# mcu.net
KiCad netlist of a schematic drawn in Altium Designer
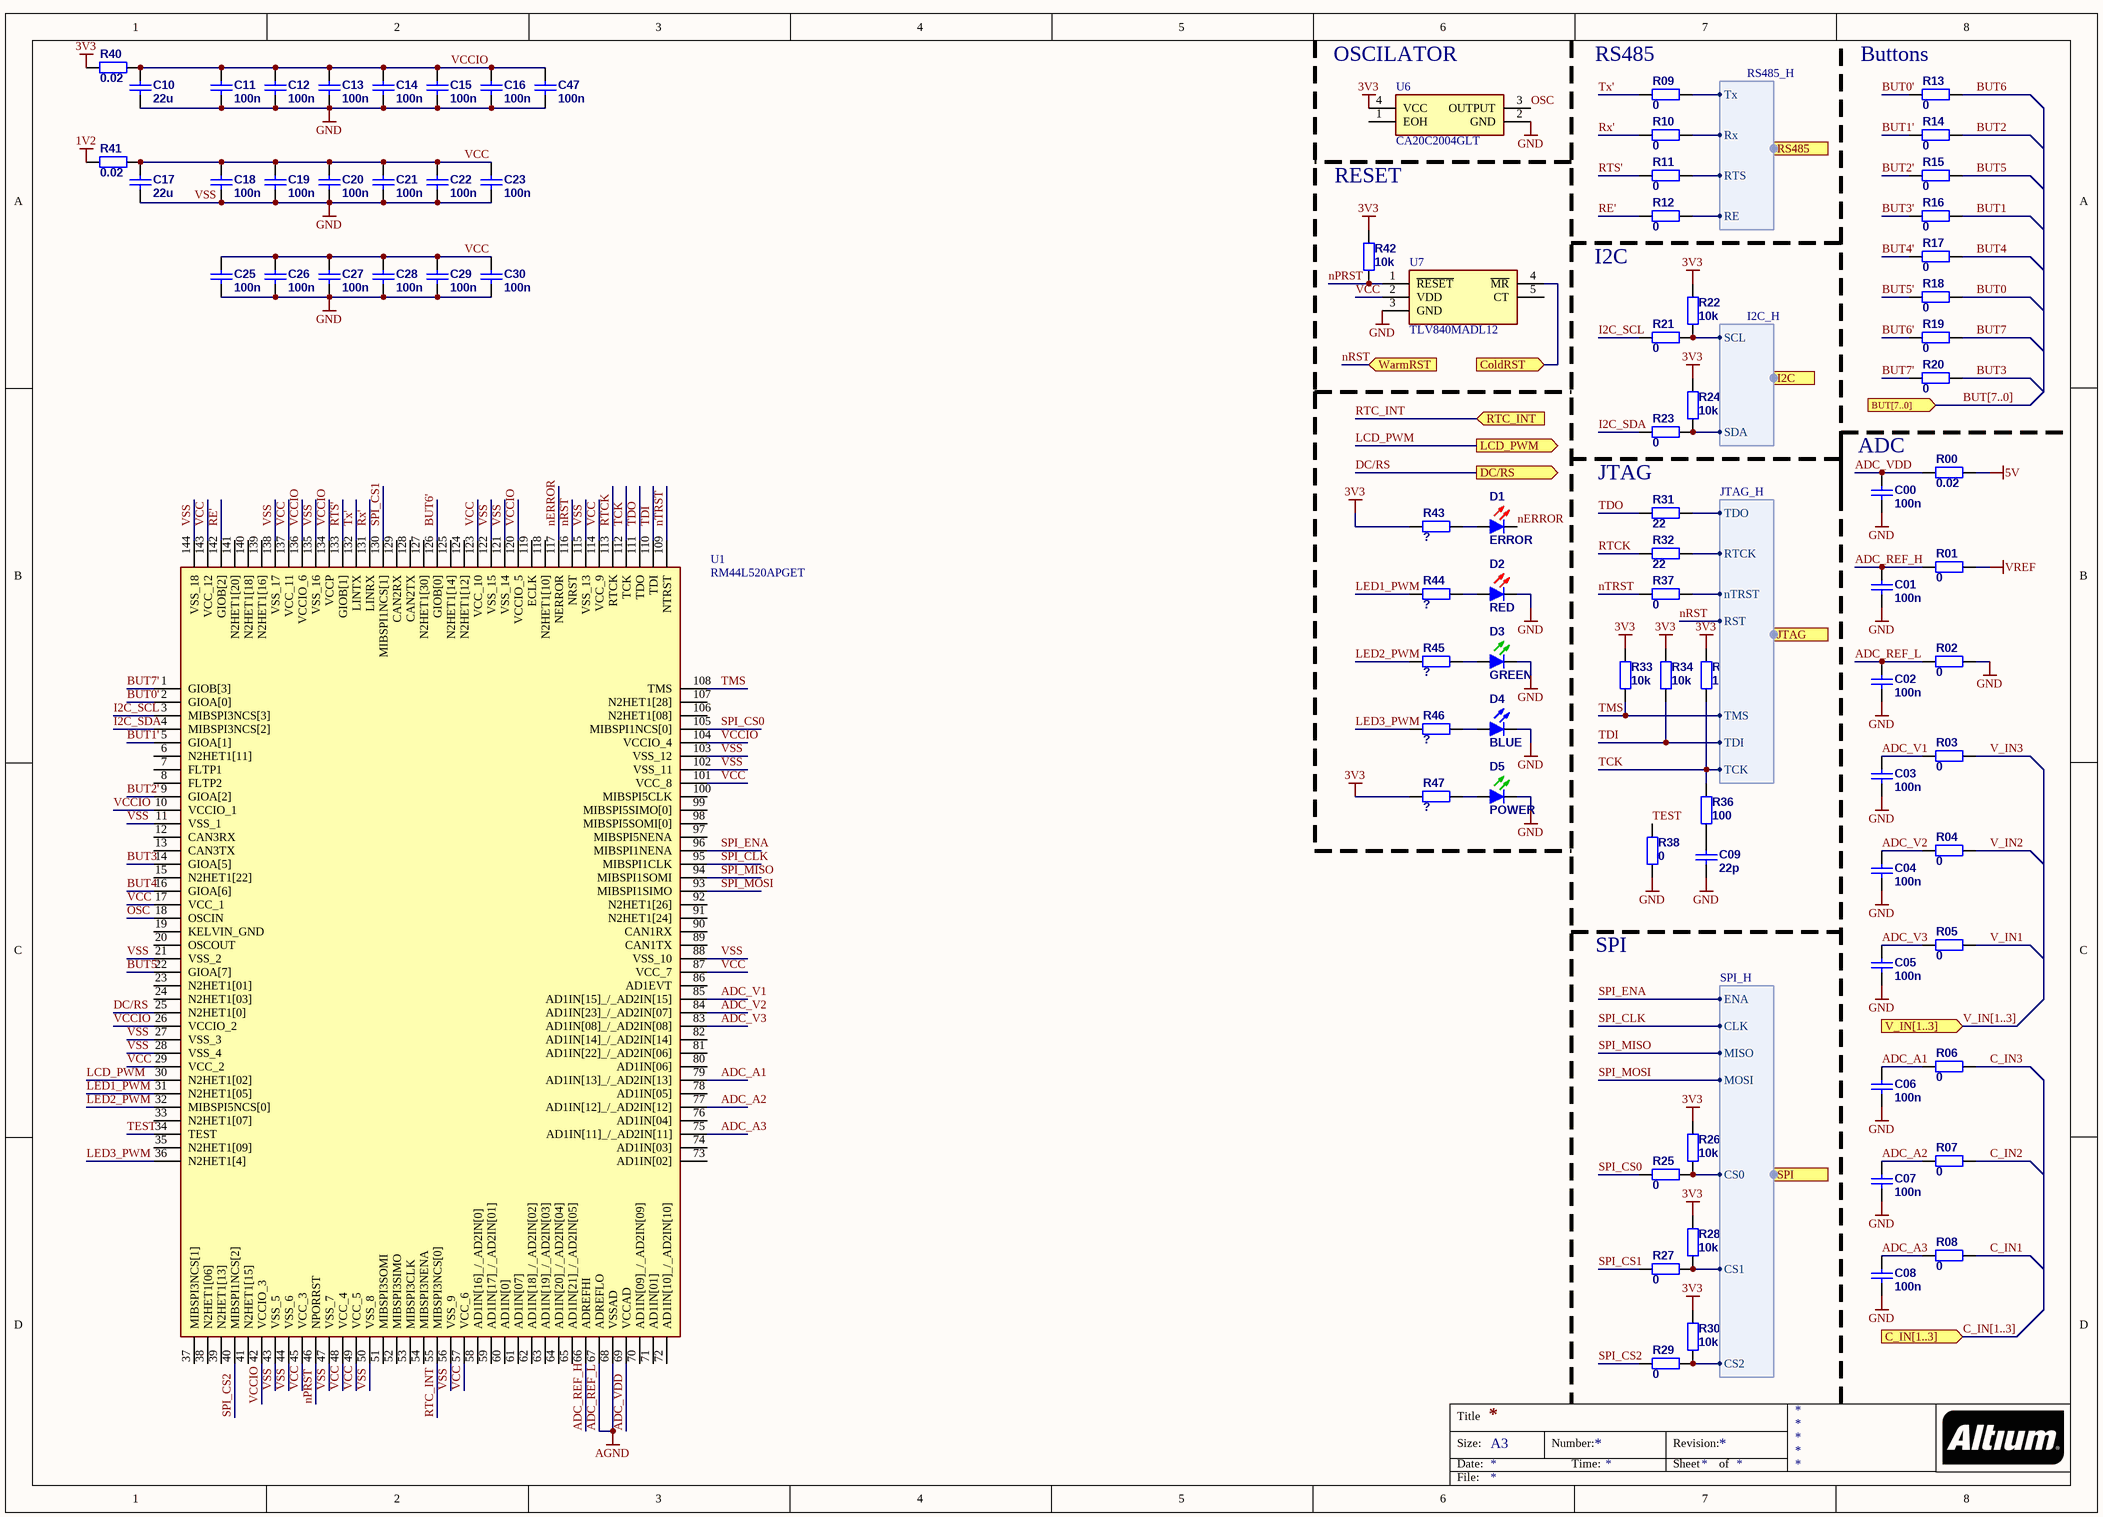
[diagram p0: mcu.SchDoc]

(export (version "E")
  (design (tool "Eeschema 10.0.6"))
  (components
    (comp (ref "C00")
      (value "100n")
      (footprint "C0402")
      (description "Capacitor")
      (libsource (lib "capacitors") (part "Cap"))
    )
    (comp (ref "C01")
      (value "100n")
      (footprint "C0402")
      (description "Capacitor")
      (libsource (lib "capacitors") (part "Cap"))
    )
    (comp (ref "C02")
      (value "100n")
      (footprint "C0402")
      (description "Capacitor")
      (libsource (lib "capacitors") (part "Cap"))
    )
    (comp (ref "C03")
      (value "100n")
      (footprint "C0402")
      (description "Capacitor")
      (libsource (lib "capacitors") (part "Cap"))
    )
    (comp (ref "C04")
      (value "100n")
      (footprint "C0402")
      (description "Capacitor")
      (libsource (lib "capacitors") (part "Cap"))
    )
    (comp (ref "C05")
      (value "100n")
      (footprint "C0402")
      (description "Capacitor")
      (libsource (lib "capacitors") (part "Cap"))
    )
    (comp (ref "C06")
      (value "100n")
      (footprint "C0402")
      (description "Capacitor")
      (libsource (lib "capacitors") (part "Cap"))
    )
    (comp (ref "C07")
      (value "100n")
      (footprint "C0402")
      (description "Capacitor")
      (libsource (lib "capacitors") (part "Cap"))
    )
    (comp (ref "C08")
      (value "100n")
      (footprint "C0402")
      (description "Capacitor")
      (libsource (lib "capacitors") (part "Cap"))
    )
    (comp (ref "C09")
      (value "22p")
      (footprint "C0402")
      (description "Capacitor")
      (libsource (lib "capacitors") (part "Cap"))
    )
    (comp (ref "C10")
      (value "22u")
      (footprint "C0603")
      (description "Capacitor")
      (libsource (lib "capacitors") (part "Cap"))
    )
    (comp (ref "C11")
      (value "100n")
      (footprint "C0402")
      (description "Capacitor")
      (libsource (lib "capacitors") (part "Cap"))
    )
    (comp (ref "C12")
      (value "100n")
      (footprint "C0402")
      (description "Capacitor")
      (libsource (lib "capacitors") (part "Cap"))
    )
    (comp (ref "C13")
      (value "100n")
      (footprint "C0402")
      (description "Capacitor")
      (libsource (lib "capacitors") (part "Cap"))
    )
    (comp (ref "C14")
      (value "100n")
      (footprint "C0402")
      (description "Capacitor")
      (libsource (lib "capacitors") (part "Cap"))
    )
    (comp (ref "C15")
      (value "100n")
      (footprint "C0402")
      (description "Capacitor")
      (libsource (lib "capacitors") (part "Cap"))
    )
    (comp (ref "C16")
      (value "100n")
      (footprint "C0402")
      (description "Capacitor")
      (libsource (lib "capacitors") (part "Cap"))
    )
    (comp (ref "C17")
      (value "22u")
      (footprint "C0603")
      (description "Capacitor")
      (libsource (lib "capacitors") (part "Cap"))
    )
    (comp (ref "C18")
      (value "100n")
      (footprint "C0402")
      (description "Capacitor")
      (libsource (lib "capacitors") (part "Cap"))
    )
    (comp (ref "C19")
      (value "100n")
      (footprint "C0402")
      (description "Capacitor")
      (libsource (lib "capacitors") (part "Cap"))
    )
    (comp (ref "C20")
      (value "100n")
      (footprint "C0402")
      (description "Capacitor")
      (libsource (lib "capacitors") (part "Cap"))
    )
    (comp (ref "C21")
      (value "100n")
      (footprint "C0402")
      (description "Capacitor")
      (libsource (lib "capacitors") (part "Cap"))
    )
    (comp (ref "C22")
      (value "100n")
      (footprint "C0402")
      (description "Capacitor")
      (libsource (lib "capacitors") (part "Cap"))
    )
    (comp (ref "C23")
      (value "100n")
      (footprint "C0402")
      (description "Capacitor")
      (libsource (lib "capacitors") (part "Cap"))
    )
    (comp (ref "C25")
      (value "100n")
      (footprint "C0402")
      (description "Capacitor")
      (libsource (lib "capacitors") (part "Cap"))
    )
    (comp (ref "C26")
      (value "100n")
      (footprint "C0402")
      (description "Capacitor")
      (libsource (lib "capacitors") (part "Cap"))
    )
    (comp (ref "C27")
      (value "100n")
      (footprint "C0402")
      (description "Capacitor")
      (libsource (lib "capacitors") (part "Cap"))
    )
    (comp (ref "C28")
      (value "100n")
      (footprint "C0402")
      (description "Capacitor")
      (libsource (lib "capacitors") (part "Cap"))
    )
    (comp (ref "C29")
      (value "100n")
      (footprint "C0402")
      (description "Capacitor")
      (libsource (lib "capacitors") (part "Cap"))
    )
    (comp (ref "C30")
      (value "100n")
      (footprint "C0402")
      (description "Capacitor")
      (libsource (lib "capacitors") (part "Cap"))
    )
    (comp (ref "C47")
      (value "100n")
      (footprint "C0402")
      (description "Capacitor")
      (libsource (lib "capacitors") (part "Cap"))
    )
    (comp (ref "D1")
      (value "ERROR")
      (footprint "LED1206R")
      (description "RED LED")
      (libsource (lib "leds") (part "LED_RED"))
    )
    (comp (ref "D2")
      (value "RED")
      (footprint "LED1206R")
      (description "RED LED")
      (libsource (lib "leds") (part "LED_RED"))
    )
    (comp (ref "D3")
      (value "GREEN")
      (footprint "LED1206G")
      (description "GREEN LED")
      (libsource (lib "leds") (part "LED_GREEN"))
    )
    (comp (ref "D4")
      (value "BLUE")
      (footprint "LED1206B")
      (description "BLUE LED")
      (libsource (lib "leds") (part "LED_BLUE"))
    )
    (comp (ref "D5")
      (value "POWER")
      (footprint "LED1206G")
      (description "GREEN LED")
      (libsource (lib "leds") (part "LED_GREEN"))
    )
    (comp (ref "R00")
      (value "0.02")
      (footprint "R0402")
      (description "Resistor")
      (libsource (lib "resistors") (part "Res"))
    )
    (comp (ref "R01")
      (value "0")
      (footprint "R0402")
      (description "Resistor")
      (libsource (lib "resistors") (part "Res"))
    )
    (comp (ref "R02")
      (value "0")
      (footprint "R0402")
      (description "Resistor")
      (libsource (lib "resistors") (part "Res"))
    )
    (comp (ref "R03")
      (value "0")
      (footprint "R0402")
      (description "Resistor")
      (libsource (lib "resistors") (part "Res"))
    )
    (comp (ref "R04")
      (value "0")
      (footprint "R0402")
      (description "Resistor")
      (libsource (lib "resistors") (part "Res"))
    )
    (comp (ref "R05")
      (value "0")
      (footprint "R0402")
      (description "Resistor")
      (libsource (lib "resistors") (part "Res"))
    )
    (comp (ref "R06")
      (value "0")
      (footprint "R0402")
      (description "Resistor")
      (libsource (lib "resistors") (part "Res"))
    )
    (comp (ref "R07")
      (value "0")
      (footprint "R0402")
      (description "Resistor")
      (libsource (lib "resistors") (part "Res"))
    )
    (comp (ref "R08")
      (value "0")
      (footprint "R0402")
      (description "Resistor")
      (libsource (lib "resistors") (part "Res"))
    )
    (comp (ref "R09")
      (value "0")
      (footprint "R0402")
      (description "Resistor")
      (libsource (lib "resistors") (part "Res"))
    )
    (comp (ref "R10")
      (value "0")
      (footprint "R0402")
      (description "Resistor")
      (libsource (lib "resistors") (part "Res"))
    )
    (comp (ref "R11")
      (value "0")
      (footprint "R0402")
      (description "Resistor")
      (libsource (lib "resistors") (part "Res"))
    )
    (comp (ref "R12")
      (value "0")
      (footprint "R0402")
      (description "Resistor")
      (libsource (lib "resistors") (part "Res"))
    )
    (comp (ref "R13")
      (value "0")
      (footprint "R0402")
      (description "Resistor")
      (libsource (lib "resistors") (part "Res"))
    )
    (comp (ref "R14")
      (value "0")
      (footprint "R0402")
      (description "Resistor")
      (libsource (lib "resistors") (part "Res"))
    )
    (comp (ref "R15")
      (value "0")
      (footprint "R0402")
      (description "Resistor")
      (libsource (lib "resistors") (part "Res"))
    )
    (comp (ref "R16")
      (value "0")
      (footprint "R0402")
      (description "Resistor")
      (libsource (lib "resistors") (part "Res"))
    )
    (comp (ref "R17")
      (value "0")
      (footprint "R0402")
      (description "Resistor")
      (libsource (lib "resistors") (part "Res"))
    )
    (comp (ref "R18")
      (value "0")
      (footprint "R0402")
      (description "Resistor")
      (libsource (lib "resistors") (part "Res"))
    )
    (comp (ref "R19")
      (value "0")
      (footprint "R0402")
      (description "Resistor")
      (libsource (lib "resistors") (part "Res"))
    )
    (comp (ref "R20")
      (value "0")
      (footprint "R0402")
      (description "Resistor")
      (libsource (lib "resistors") (part "Res"))
    )
    (comp (ref "R21")
      (value "0")
      (footprint "R0402")
      (description "Resistor")
      (libsource (lib "resistors") (part "Res"))
    )
    (comp (ref "R22")
      (value "10k")
      (footprint "R0402")
      (description "Resistor")
      (libsource (lib "") (part "Res_1"))
    )
    (comp (ref "R23")
      (value "0")
      (footprint "R0402")
      (description "Resistor")
      (libsource (lib "") (part "Res_2"))
    )
    (comp (ref "R24")
      (value "10k")
      (footprint "R0402")
      (description "Resistor")
      (libsource (lib "") (part "Res_3"))
    )
    (comp (ref "R25")
      (value "0")
      (footprint "R0402")
      (description "Resistor")
      (libsource (lib "resistors") (part "Res"))
    )
    (comp (ref "R26")
      (value "10k")
      (footprint "R0402")
      (description "Resistor")
      (libsource (lib "") (part "Res_1"))
    )
    (comp (ref "R27")
      (value "0")
      (footprint "R0402")
      (description "Resistor")
      (libsource (lib "") (part "Res_2"))
    )
    (comp (ref "R28")
      (value "10k")
      (footprint "R0402")
      (description "Resistor")
      (libsource (lib "") (part "Res_1"))
    )
    (comp (ref "R29")
      (value "0")
      (footprint "R0402")
      (description "Resistor")
      (libsource (lib "") (part "Res_2"))
    )
    (comp (ref "R30")
      (value "10k")
      (footprint "R0402")
      (description "Resistor")
      (libsource (lib "") (part "Res_3"))
    )
    (comp (ref "R31")
      (value "22")
      (footprint "R0402")
      (description "Resistor")
      (libsource (lib "resistors") (part "Res"))
    )
    (comp (ref "R32")
      (value "22")
      (footprint "R0402")
      (description "Resistor")
      (libsource (lib "resistors") (part "Res"))
    )
    (comp (ref "R33")
      (value "10k")
      (footprint "R0402")
      (description "Resistor")
      (libsource (lib "") (part "Res_1"))
    )
    (comp (ref "R34")
      (value "10k")
      (footprint "R0402")
      (description "Resistor")
      (libsource (lib "") (part "Res_1"))
    )
    (comp (ref "R35")
      (value "10k")
      (footprint "R0402")
      (description "Resistor")
      (libsource (lib "") (part "Res_1"))
    )
    (comp (ref "R36")
      (value "100")
      (footprint "R0402")
      (description "Resistor")
      (libsource (lib "") (part "Res_1"))
    )
    (comp (ref "R37")
      (value "0")
      (footprint "R0402")
      (description "Resistor")
      (libsource (lib "resistors") (part "Res"))
    )
    (comp (ref "R38")
      (value "0")
      (footprint "R0402")
      (description "Resistor")
      (libsource (lib "") (part "Res_1"))
    )
    (comp (ref "R40")
      (value "0.02")
      (footprint "R0603")
      (description "Resistor")
      (libsource (lib "resistors") (part "Res"))
    )
    (comp (ref "R41")
      (value "0.02")
      (footprint "R0603")
      (description "Resistor")
      (libsource (lib "resistors") (part "Res"))
    )
    (comp (ref "R42")
      (value "10k")
      (footprint "R0402")
      (description "Resistor")
      (libsource (lib "") (part "Res_1"))
    )
    (comp (ref "R43")
      (value "?")
      (footprint "R0603")
      (description "Resistor")
      (libsource (lib "") (part "Res_2"))
    )
    (comp (ref "R44")
      (value "?")
      (footprint "R0402")
      (description "Resistor")
      (libsource (lib "") (part "Res_2"))
    )
    (comp (ref "R45")
      (value "?")
      (footprint "R0402")
      (description "Resistor")
      (libsource (lib "") (part "Res_2"))
    )
    (comp (ref "R46")
      (value "?")
      (footprint "R0402")
      (description "Resistor")
      (libsource (lib "") (part "Res_2"))
    )
    (comp (ref "R47")
      (value "?")
      (footprint "R0603")
      (description "Resistor")
      (libsource (lib "") (part "Res_2"))
    )
    (comp (ref "U1")
      (value "RM44L520APGET")
      (footprint "SamacSys:QFP50P2200X2200X160-144N")
      (description "Integrated Circuit")
      (fields (field (name "MOUSER2 PART NUMBER") "595-RM44L520APGET"))
      (libsource (lib "*") (part "RM44L520APGET"))
    )
    (comp (ref "U6")
      (value "CA20C2004GLT")
      (footprint "SamacSys:CA20C2004GLT")
      (description "Crystal or Oscillator")
      (fields (field (name "MOUSER2 PART NUMBER") "774-CA20C2004GLT"))
      (libsource (lib "*") (part "CA20C2004GLT"))
    )
    (comp (ref "U7")
      (value "TLV840MADL12")
      (footprint "SamacSys:SOT95P280X145-5N")
      (description "Integrated Circuit")
      (fields (field (name "MANUFACTURER_PART_NUMBER") "TLV840MAPL36DBVRQ1"))
      (libsource (lib "*") (part "TLV840MAPL36DBVRQ1"))
    )
  )
  (nets
    (net (code "5") (name "/ADC_A1") (class "Default")
      (node (ref "C06") (pin "2") (pinfunction "2_2") (pintype "passive"))
      (node (ref "R06") (pin "1") (pinfunction "1_1") (pintype "passive"))
      (node (ref "U1") (pin "79") (pinfunction "AD1IN[13]_/_AD2IN[13]_79") (pintype "passive"))
    )
    (net (code "6") (name "/ADC_A2") (class "Default")
      (node (ref "C07") (pin "2") (pinfunction "2_2") (pintype "passive"))
      (node (ref "R07") (pin "1") (pinfunction "1_1") (pintype "passive"))
      (node (ref "U1") (pin "77") (pinfunction "AD1IN[12]_/_AD2IN[12]_77") (pintype "passive"))
    )
    (net (code "7") (name "/ADC_A3") (class "Default")
      (node (ref "C08") (pin "2") (pinfunction "2_2") (pintype "passive"))
      (node (ref "R08") (pin "1") (pinfunction "1_1") (pintype "passive"))
      (node (ref "U1") (pin "75") (pinfunction "AD1IN[11]_/_AD2IN[11]_75") (pintype "passive"))
    )
    (net (code "8") (name "/ADC_REF_H") (class "Default")
      (node (ref "C01") (pin "2") (pinfunction "2_2") (pintype "passive"))
      (node (ref "R01") (pin "1") (pinfunction "1_1") (pintype "passive"))
      (node (ref "U1") (pin "66") (pinfunction "ADREFHI_66") (pintype "passive"))
    )
    (net (code "9") (name "/ADC_V1") (class "Default")
      (node (ref "C03") (pin "2") (pinfunction "2_2") (pintype "passive"))
      (node (ref "R03") (pin "1") (pinfunction "1_1") (pintype "passive"))
      (node (ref "U1") (pin "85") (pinfunction "AD1IN[15]_/_AD2IN[15]_85") (pintype "passive"))
    )
    (net (code "10") (name "/ADC_V2") (class "Default")
      (node (ref "C04") (pin "2") (pinfunction "2_2") (pintype "passive"))
      (node (ref "R04") (pin "1") (pinfunction "1_1") (pintype "passive"))
      (node (ref "U1") (pin "84") (pinfunction "AD1IN[23]_/_AD2IN[07]_84") (pintype "passive"))
    )
    (net (code "11") (name "/ADC_V3") (class "Default")
      (node (ref "C05") (pin "2") (pinfunction "2_2") (pintype "passive"))
      (node (ref "R05") (pin "1") (pinfunction "1_1") (pintype "passive"))
      (node (ref "U1") (pin "83") (pinfunction "AD1IN[08]_/_AD2IN[08]_83") (pintype "passive"))
    )
    (net (code "12") (name "/ADC_VDD") (class "Default")
      (node (ref "C00") (pin "2") (pinfunction "2_2") (pintype "passive"))
      (node (ref "R00") (pin "1") (pinfunction "1_1") (pintype "passive"))
      (node (ref "U1") (pin "69") (pinfunction "VCCAD_69") (pintype "passive"))
    )
    (net (code "13") (name "/BUT0") (class "Default")
      (node (ref "R18") (pin "2") (pinfunction "2_2") (pintype "passive"))
    )
    (net (code "14") (name "/BUT0'") (class "Default")
      (node (ref "R13") (pin "1") (pinfunction "1_1") (pintype "passive"))
      (node (ref "U1") (pin "2") (pinfunction "GIOA[0]_2") (pintype "passive"))
    )
    (net (code "15") (name "/BUT1") (class "Default")
      (node (ref "R16") (pin "2") (pinfunction "2_2") (pintype "passive"))
    )
    (net (code "16") (name "/BUT1'") (class "Default")
      (node (ref "R14") (pin "1") (pinfunction "1_1") (pintype "passive"))
      (node (ref "U1") (pin "5") (pinfunction "GIOA[1]_5") (pintype "passive"))
    )
    (net (code "17") (name "/BUT2") (class "Default")
      (node (ref "R14") (pin "2") (pinfunction "2_2") (pintype "passive"))
    )
    (net (code "18") (name "/BUT2'") (class "Default")
      (node (ref "R15") (pin "1") (pinfunction "1_1") (pintype "passive"))
      (node (ref "U1") (pin "9") (pinfunction "GIOA[2]_9") (pintype "passive"))
    )
    (net (code "19") (name "/BUT3") (class "Default")
      (node (ref "R20") (pin "2") (pinfunction "2_2") (pintype "passive"))
    )
    (net (code "20") (name "/BUT3'") (class "Default")
      (node (ref "R16") (pin "1") (pinfunction "1_1") (pintype "passive"))
      (node (ref "U1") (pin "14") (pinfunction "GIOA[5]_14") (pintype "passive"))
    )
    (net (code "21") (name "/BUT4") (class "Default")
      (node (ref "R17") (pin "2") (pinfunction "2_2") (pintype "passive"))
    )
    (net (code "22") (name "/BUT4'") (class "Default")
      (node (ref "R17") (pin "1") (pinfunction "1_1") (pintype "passive"))
      (node (ref "U1") (pin "16") (pinfunction "GIOA[6]_16") (pintype "passive"))
    )
    (net (code "23") (name "/BUT5") (class "Default")
      (node (ref "R15") (pin "2") (pinfunction "2_2") (pintype "passive"))
    )
    (net (code "24") (name "/BUT5'") (class "Default")
      (node (ref "R18") (pin "1") (pinfunction "1_1") (pintype "passive"))
      (node (ref "U1") (pin "22") (pinfunction "GIOA[7]_22") (pintype "passive"))
    )
    (net (code "25") (name "/BUT6") (class "Default")
      (node (ref "R13") (pin "2") (pinfunction "2_2") (pintype "passive"))
    )
    (net (code "26") (name "/BUT6'") (class "Default")
      (node (ref "R19") (pin "1") (pinfunction "1_1") (pintype "passive"))
      (node (ref "U1") (pin "126") (pinfunction "GIOB[0]_126") (pintype "passive"))
    )
    (net (code "27") (name "/BUT7") (class "Default")
      (node (ref "R19") (pin "2") (pinfunction "2_2") (pintype "passive"))
    )
    (net (code "28") (name "/BUT7'") (class "Default")
      (node (ref "R20") (pin "1") (pinfunction "1_1") (pintype "passive"))
      (node (ref "U1") (pin "1") (pinfunction "GIOB[3]_1") (pintype "passive"))
    )
    (net (code "30") (name "/CS0") (class "Default")
      (node (ref "R25") (pin "2") (pinfunction "2_2") (pintype "passive"))
      (node (ref "R26") (pin "1") (pinfunction "1_1") (pintype "passive"))
    )
    (net (code "31") (name "/CS1") (class "Default")
      (node (ref "R27") (pin "1") (pinfunction "1_1") (pintype "passive"))
      (node (ref "R28") (pin "1") (pinfunction "1_1") (pintype "passive"))
    )
    (net (code "32") (name "/CS2") (class "Default")
      (node (ref "R29") (pin "1") (pinfunction "1_1") (pintype "passive"))
      (node (ref "R30") (pin "2") (pinfunction "2_2") (pintype "passive"))
    )
    (net (code "33") (name "/C_IN1") (class "Default")
      (node (ref "R08") (pin "2") (pinfunction "2_2") (pintype "passive"))
    )
    (net (code "34") (name "/C_IN2") (class "Default")
      (node (ref "R07") (pin "2") (pinfunction "2_2") (pintype "passive"))
    )
    (net (code "35") (name "/C_IN3") (class "Default")
      (node (ref "R06") (pin "2") (pinfunction "2_2") (pintype "passive"))
    )
    (net (code "37") (name "/ColdRST") (class "Default")
      (node (ref "U7") (pin "4") (pinfunction "~{MR}_4") (pintype "passive"))
    )
    (net (code "38") (name "/DC{slash}RS") (class "Default")
      (node (ref "U1") (pin "25") (pinfunction "N2HET1[0]_25") (pintype "passive"))
    )
    (net (code "39") (name "/I2C_SCL") (class "Default")
      (node (ref "R21") (pin "1") (pinfunction "1_1") (pintype "passive"))
      (node (ref "U1") (pin "3") (pinfunction "MIBSPI3NCS[3]_3") (pintype "passive"))
    )
    (net (code "40") (name "/I2C_SDA") (class "Default")
      (node (ref "R23") (pin "2") (pinfunction "2_2") (pintype "passive"))
      (node (ref "U1") (pin "4") (pinfunction "MIBSPI3NCS[2]_4") (pintype "passive"))
    )
    (net (code "41") (name "/LCD_PWM") (class "Default")
      (node (ref "U1") (pin "30") (pinfunction "N2HET1[02]_30") (pintype "passive"))
    )
    (net (code "42") (name "/LED1_PWM") (class "Default")
      (node (ref "R44") (pin "2") (pinfunction "2_2") (pintype "passive"))
      (node (ref "U1") (pin "31") (pinfunction "N2HET1[05]_31") (pintype "passive"))
    )
    (net (code "43") (name "/LED2_PWM") (class "Default")
      (node (ref "R45") (pin "2") (pinfunction "2_2") (pintype "passive"))
      (node (ref "U1") (pin "32") (pinfunction "MIBSPI5NCS[0]_32") (pintype "passive"))
    )
    (net (code "44") (name "/LED3_PWM") (class "Default")
      (node (ref "R46") (pin "2") (pinfunction "2_2") (pintype "passive"))
      (node (ref "U1") (pin "36") (pinfunction "N2HET1[4]_36") (pintype "passive"))
    )
    (net (code "45") (name "/OSC") (class "Default")
      (node (ref "U1") (pin "18") (pinfunction "OSCIN_18") (pintype "passive"))
      (node (ref "U6") (pin "3") (pinfunction "OUTPUT_3") (pintype "passive"))
    )
    (net (code "46") (name "/RE") (class "Default")
      (node (ref "R12") (pin "2") (pinfunction "2_2") (pintype "passive"))
    )
    (net (code "47") (name "/RE'") (class "Default")
      (node (ref "R12") (pin "1") (pinfunction "1_1") (pintype "passive"))
      (node (ref "U1") (pin "142") (pinfunction "GIOB[2]_142") (pintype "passive"))
    )
    (net (code "48") (name "/RTCK") (class "Default")
      (node (ref "R32") (pin "1") (pinfunction "1_1") (pintype "passive"))
      (node (ref "U1") (pin "113") (pinfunction "RTCK_113") (pintype "passive"))
    )
    (net (code "49") (name "/RTC_INT") (class "Default")
      (node (ref "U1") (pin "55") (pinfunction "MIBSPI3NCS[0]_55") (pintype "passive"))
    )
    (net (code "50") (name "/RTS") (class "Default")
      (node (ref "R11") (pin "2") (pinfunction "2_2") (pintype "passive"))
    )
    (net (code "51") (name "/RTS'") (class "Default")
      (node (ref "R11") (pin "1") (pinfunction "1_1") (pintype "passive"))
      (node (ref "U1") (pin "133") (pinfunction "GIOB[1]_133") (pintype "passive"))
    )
    (net (code "52") (name "/Rx") (class "Default")
      (node (ref "R10") (pin "2") (pinfunction "2_2") (pintype "passive"))
    )
    (net (code "53") (name "/Rx'") (class "Default")
      (node (ref "R10") (pin "1") (pinfunction "1_1") (pintype "passive"))
      (node (ref "U1") (pin "131") (pinfunction "LINRX_131") (pintype "passive"))
    )
    (net (code "54") (name "/SCL") (class "Default")
      (node (ref "R21") (pin "2") (pinfunction "2_2") (pintype "passive"))
      (node (ref "R22") (pin "1") (pinfunction "1_1") (pintype "passive"))
    )
    (net (code "55") (name "/SDA") (class "Default")
      (node (ref "R23") (pin "1") (pinfunction "1_1") (pintype "passive"))
      (node (ref "R24") (pin "2") (pinfunction "2_2") (pintype "passive"))
    )
    (net (code "56") (name "/SPI_CLK") (class "Default")
      (node (ref "U1") (pin "95") (pinfunction "MIBSPI1CLK_95") (pintype "passive"))
    )
    (net (code "57") (name "/SPI_CS0") (class "Default")
      (node (ref "R25") (pin "1") (pinfunction "1_1") (pintype "passive"))
      (node (ref "U1") (pin "105") (pinfunction "MIBSPI1NCS[0]_105") (pintype "passive"))
    )
    (net (code "58") (name "/SPI_CS1") (class "Default")
      (node (ref "R27") (pin "2") (pinfunction "2_2") (pintype "passive"))
      (node (ref "U1") (pin "130") (pinfunction "MIBSPI1NCS[1]_130") (pintype "passive"))
    )
    (net (code "59") (name "/SPI_CS2") (class "Default")
      (node (ref "R29") (pin "2") (pinfunction "2_2") (pintype "passive"))
      (node (ref "U1") (pin "40") (pinfunction "MIBSPI1NCS[2]_40") (pintype "passive"))
    )
    (net (code "60") (name "/SPI_ENA") (class "Default")
      (node (ref "U1") (pin "96") (pinfunction "MIBSPI1NENA_96") (pintype "passive"))
    )
    (net (code "61") (name "/SPI_MISO") (class "Default")
      (node (ref "U1") (pin "94") (pinfunction "MIBSPI1SOMI_94") (pintype "passive"))
    )
    (net (code "62") (name "/SPI_MOSI") (class "Default")
      (node (ref "U1") (pin "93") (pinfunction "MIBSPI1SIMO_93") (pintype "passive"))
    )
    (net (code "63") (name "/TCK") (class "Default")
      (node (ref "R35") (pin "1") (pinfunction "1_1") (pintype "passive"))
      (node (ref "R36") (pin "2") (pinfunction "2_2") (pintype "passive"))
      (node (ref "U1") (pin "112") (pinfunction "TCK_112") (pintype "passive"))
    )
    (net (code "64") (name "/TDI") (class "Default")
      (node (ref "R34") (pin "1") (pinfunction "1_1") (pintype "passive"))
      (node (ref "U1") (pin "110") (pinfunction "TDI_110") (pintype "passive"))
    )
    (net (code "65") (name "/TDO") (class "Default")
      (node (ref "R31") (pin "1") (pinfunction "1_1") (pintype "passive"))
      (node (ref "U1") (pin "111") (pinfunction "TDO_111") (pintype "passive"))
    )
    (net (code "66") (name "/TEST") (class "Default")
      (node (ref "R38") (pin "2") (pinfunction "2_2") (pintype "passive"))
      (node (ref "U1") (pin "34") (pinfunction "TEST_34") (pintype "passive"))
    )
    (net (code "67") (name "/TMS") (class "Default")
      (node (ref "R33") (pin "1") (pinfunction "1_1") (pintype "passive"))
      (node (ref "U1") (pin "108") (pinfunction "TMS_108") (pintype "passive"))
    )
    (net (code "68") (name "/Tx") (class "Default")
      (node (ref "R09") (pin "2") (pinfunction "2_2") (pintype "passive"))
    )
    (net (code "69") (name "/Tx'") (class "Default")
      (node (ref "R09") (pin "1") (pinfunction "1_1") (pintype "passive"))
      (node (ref "U1") (pin "132") (pinfunction "LINTX_132") (pintype "passive"))
    )
    (net (code "70") (name "/VCC") (class "Default")
      (node (ref "C17") (pin "2") (pinfunction "2_2") (pintype "passive"))
      (node (ref "C18") (pin "2") (pinfunction "2_2") (pintype "passive"))
      (node (ref "C19") (pin "2") (pinfunction "2_2") (pintype "passive"))
      (node (ref "C20") (pin "2") (pinfunction "2_2") (pintype "passive"))
      (node (ref "C21") (pin "2") (pinfunction "2_2") (pintype "passive"))
      (node (ref "C22") (pin "2") (pinfunction "2_2") (pintype "passive"))
      (node (ref "C23") (pin "2") (pinfunction "2_2") (pintype "passive"))
      (node (ref "C25") (pin "2") (pinfunction "2_2") (pintype "passive"))
      (node (ref "C26") (pin "2") (pinfunction "2_2") (pintype "passive"))
      (node (ref "C27") (pin "2") (pinfunction "2_2") (pintype "passive"))
      (node (ref "C28") (pin "2") (pinfunction "2_2") (pintype "passive"))
      (node (ref "C29") (pin "2") (pinfunction "2_2") (pintype "passive"))
      (node (ref "C30") (pin "2") (pinfunction "2_2") (pintype "passive"))
      (node (ref "R41") (pin "2") (pinfunction "2_2") (pintype "passive"))
      (node (ref "U1") (pin "101") (pinfunction "VCC_8_101") (pintype "passive"))
      (node (ref "U1") (pin "114") (pinfunction "VCC_9_114") (pintype "passive"))
      (node (ref "U1") (pin "123") (pinfunction "VCC_10_123") (pintype "passive"))
      (node (ref "U1") (pin "137") (pinfunction "VCC_11_137") (pintype "passive"))
      (node (ref "U1") (pin "143") (pinfunction "VCC_12_143") (pintype "passive"))
      (node (ref "U1") (pin "17") (pinfunction "VCC_1_17") (pintype "passive"))
      (node (ref "U1") (pin "29") (pinfunction "VCC_2_29") (pintype "passive"))
      (node (ref "U1") (pin "45") (pinfunction "VCC_3_45") (pintype "passive"))
      (node (ref "U1") (pin "48") (pinfunction "VCC_4_48") (pintype "passive"))
      (node (ref "U1") (pin "49") (pinfunction "VCC_5_49") (pintype "passive"))
      (node (ref "U1") (pin "57") (pinfunction "VCC_6_57") (pintype "passive"))
      (node (ref "U1") (pin "87") (pinfunction "VCC_7_87") (pintype "passive"))
      (node (ref "U7") (pin "2") (pinfunction "VDD_2") (pintype "passive"))
    )
    (net (code "71") (name "/VCCIO") (class "Default")
      (node (ref "C10") (pin "2") (pinfunction "2_2") (pintype "passive"))
      (node (ref "C11") (pin "2") (pinfunction "2_2") (pintype "passive"))
      (node (ref "C12") (pin "2") (pinfunction "2_2") (pintype "passive"))
      (node (ref "C13") (pin "2") (pinfunction "2_2") (pintype "passive"))
      (node (ref "C14") (pin "2") (pinfunction "2_2") (pintype "passive"))
      (node (ref "C15") (pin "2") (pinfunction "2_2") (pintype "passive"))
      (node (ref "C16") (pin "2") (pinfunction "2_2") (pintype "passive"))
      (node (ref "C47") (pin "2") (pinfunction "2_2") (pintype "passive"))
      (node (ref "R40") (pin "2") (pinfunction "2_2") (pintype "passive"))
      (node (ref "U1") (pin "10") (pinfunction "VCCIO_1_10") (pintype "passive"))
      (node (ref "U1") (pin "104") (pinfunction "VCCIO_4_104") (pintype "passive"))
      (node (ref "U1") (pin "120") (pinfunction "VCCIO_5_120") (pintype "passive"))
      (node (ref "U1") (pin "134") (pinfunction "VCCP_134") (pintype "passive"))
      (node (ref "U1") (pin "136") (pinfunction "VCCIO_6_136") (pintype "passive"))
      (node (ref "U1") (pin "26") (pinfunction "VCCIO_2_26") (pintype "passive"))
      (node (ref "U1") (pin "42") (pinfunction "VCCIO_3_42") (pintype "passive"))
    )
    (net (code "72") (name "/V_IN1") (class "Default")
      (node (ref "R05") (pin "2") (pinfunction "2_2") (pintype "passive"))
    )
    (net (code "73") (name "/V_IN2") (class "Default")
      (node (ref "R04") (pin "2") (pinfunction "2_2") (pintype "passive"))
    )
    (net (code "74") (name "/V_IN3") (class "Default")
      (node (ref "R03") (pin "2") (pinfunction "2_2") (pintype "passive"))
    )
    (net (code "76") (name "/nERROR") (class "Default")
      (node (ref "D1") (pin "2") (pinfunction "K_2") (pintype "passive"))
      (node (ref "U1") (pin "117") (pinfunction "NERROR_117") (pintype "passive"))
    )
    (net (code "77") (name "/nPRST") (class "Default")
      (node (ref "R42") (pin "1") (pinfunction "1_1") (pintype "passive"))
      (node (ref "U1") (pin "46") (pinfunction "NPORRST_46") (pintype "passive"))
      (node (ref "U7") (pin "1") (pinfunction "~{RESET}_1") (pintype "passive"))
    )
    (net (code "78") (name "/nRST") (class "Default")
      (node (ref "U1") (pin "116") (pinfunction "NRST_116") (pintype "passive"))
    )
    (net (code "79") (name "/nTRST") (class "Default")
      (node (ref "R37") (pin "1") (pinfunction "1_1") (pintype "passive"))
      (node (ref "U1") (pin "109") (pinfunction "NTRST_109") (pintype "passive"))
    )
    (net (code "84") (name "1V2") (class "Default")
      (node (ref "R41") (pin "1") (pinfunction "1_1") (pintype "passive"))
    )
    (net (code "85") (name "3V3") (class "Default")
      (node (ref "R22") (pin "2") (pinfunction "2_2") (pintype "passive"))
      (node (ref "R24") (pin "1") (pinfunction "1_1") (pintype "passive"))
      (node (ref "R26") (pin "2") (pinfunction "2_2") (pintype "passive"))
      (node (ref "R28") (pin "2") (pinfunction "2_2") (pintype "passive"))
      (node (ref "R30") (pin "1") (pinfunction "1_1") (pintype "passive"))
      (node (ref "R33") (pin "2") (pinfunction "2_2") (pintype "passive"))
      (node (ref "R34") (pin "2") (pinfunction "2_2") (pintype "passive"))
      (node (ref "R35") (pin "2") (pinfunction "2_2") (pintype "passive"))
      (node (ref "R40") (pin "1") (pinfunction "1_1") (pintype "passive"))
      (node (ref "R42") (pin "2") (pinfunction "2_2") (pintype "passive"))
      (node (ref "R43") (pin "2") (pinfunction "2_2") (pintype "passive"))
      (node (ref "R47") (pin "2") (pinfunction "2_2") (pintype "passive"))
      (node (ref "U6") (pin "4") (pinfunction "VCC_4") (pintype "passive"))
    )
    (net (code "86") (name "5V") (class "Default")
      (node (ref "R00") (pin "2") (pinfunction "2_2") (pintype "passive"))
    )
    (net (code "87") (name "AGND") (class "Default")
      (node (ref "C02") (pin "2") (pinfunction "2_2") (pintype "passive"))
      (node (ref "R02") (pin "1") (pinfunction "1_1") (pintype "passive"))
      (node (ref "U1") (pin "67") (pinfunction "ADREFLO_67") (pintype "passive"))
      (node (ref "U1") (pin "68") (pinfunction "VSSAD_68") (pintype "passive"))
    )
    (net (code "88") (name "GND") (class "Default")
      (node (ref "C00") (pin "1") (pinfunction "1_1") (pintype "passive"))
      (node (ref "C01") (pin "1") (pinfunction "1_1") (pintype "passive"))
      (node (ref "C02") (pin "1") (pinfunction "1_1") (pintype "passive"))
      (node (ref "C03") (pin "1") (pinfunction "1_1") (pintype "passive"))
      (node (ref "C04") (pin "1") (pinfunction "1_1") (pintype "passive"))
      (node (ref "C05") (pin "1") (pinfunction "1_1") (pintype "passive"))
      (node (ref "C06") (pin "1") (pinfunction "1_1") (pintype "passive"))
      (node (ref "C07") (pin "1") (pinfunction "1_1") (pintype "passive"))
      (node (ref "C08") (pin "1") (pinfunction "1_1") (pintype "passive"))
      (node (ref "C09") (pin "1") (pinfunction "1_1") (pintype "passive"))
      (node (ref "C10") (pin "1") (pinfunction "1_1") (pintype "passive"))
      (node (ref "C11") (pin "1") (pinfunction "1_1") (pintype "passive"))
      (node (ref "C12") (pin "1") (pinfunction "1_1") (pintype "passive"))
      (node (ref "C13") (pin "1") (pinfunction "1_1") (pintype "passive"))
      (node (ref "C14") (pin "1") (pinfunction "1_1") (pintype "passive"))
      (node (ref "C15") (pin "1") (pinfunction "1_1") (pintype "passive"))
      (node (ref "C16") (pin "1") (pinfunction "1_1") (pintype "passive"))
      (node (ref "C17") (pin "1") (pinfunction "1_1") (pintype "passive"))
      (node (ref "C18") (pin "1") (pinfunction "1_1") (pintype "passive"))
      (node (ref "C19") (pin "1") (pinfunction "1_1") (pintype "passive"))
      (node (ref "C20") (pin "1") (pinfunction "1_1") (pintype "passive"))
      (node (ref "C21") (pin "1") (pinfunction "1_1") (pintype "passive"))
      (node (ref "C22") (pin "1") (pinfunction "1_1") (pintype "passive"))
      (node (ref "C23") (pin "1") (pinfunction "1_1") (pintype "passive"))
      (node (ref "C25") (pin "1") (pinfunction "1_1") (pintype "passive"))
      (node (ref "C26") (pin "1") (pinfunction "1_1") (pintype "passive"))
      (node (ref "C27") (pin "1") (pinfunction "1_1") (pintype "passive"))
      (node (ref "C28") (pin "1") (pinfunction "1_1") (pintype "passive"))
      (node (ref "C29") (pin "1") (pinfunction "1_1") (pintype "passive"))
      (node (ref "C30") (pin "1") (pinfunction "1_1") (pintype "passive"))
      (node (ref "C47") (pin "1") (pinfunction "1_1") (pintype "passive"))
      (node (ref "D2") (pin "2") (pinfunction "K_2") (pintype "passive"))
      (node (ref "D3") (pin "2") (pinfunction "K_2") (pintype "passive"))
      (node (ref "D4") (pin "2") (pinfunction "K_2") (pintype "passive"))
      (node (ref "D5") (pin "2") (pinfunction "K_2") (pintype "passive"))
      (node (ref "R02") (pin "2") (pinfunction "2_2") (pintype "passive"))
      (node (ref "R38") (pin "1") (pinfunction "1_1") (pintype "passive"))
      (node (ref "U1") (pin "102") (pinfunction "VSS_11_102") (pintype "passive"))
      (node (ref "U1") (pin "103") (pinfunction "VSS_12_103") (pintype "passive"))
      (node (ref "U1") (pin "11") (pinfunction "VSS_1_11") (pintype "passive"))
      (node (ref "U1") (pin "115") (pinfunction "VSS_13_115") (pintype "passive"))
      (node (ref "U1") (pin "121") (pinfunction "VSS_14_121") (pintype "passive"))
      (node (ref "U1") (pin "122") (pinfunction "VSS_15_122") (pintype "passive"))
      (node (ref "U1") (pin "135") (pinfunction "VSS_16_135") (pintype "passive"))
      (node (ref "U1") (pin "138") (pinfunction "VSS_17_138") (pintype "passive"))
      (node (ref "U1") (pin "144") (pinfunction "VSS_18_144") (pintype "passive"))
      (node (ref "U1") (pin "21") (pinfunction "VSS_2_21") (pintype "passive"))
      (node (ref "U1") (pin "27") (pinfunction "VSS_3_27") (pintype "passive"))
      (node (ref "U1") (pin "28") (pinfunction "VSS_4_28") (pintype "passive"))
      (node (ref "U1") (pin "43") (pinfunction "VSS_5_43") (pintype "passive"))
      (node (ref "U1") (pin "44") (pinfunction "VSS_6_44") (pintype "passive"))
      (node (ref "U1") (pin "47") (pinfunction "VSS_7_47") (pintype "passive"))
      (node (ref "U1") (pin "50") (pinfunction "VSS_8_50") (pintype "passive"))
      (node (ref "U1") (pin "56") (pinfunction "VSS_9_56") (pintype "passive"))
      (node (ref "U1") (pin "88") (pinfunction "VSS_10_88") (pintype "passive"))
      (node (ref "U6") (pin "2") (pinfunction "GND_2") (pintype "passive"))
      (node (ref "U7") (pin "3") (pinfunction "GND_3") (pintype "passive"))
    )
    (net (code "89") (name "Net-(C09-Pad2)") (class "Default")
      (node (ref "C09") (pin "2") (pinfunction "2_2") (pintype "passive"))
      (node (ref "R36") (pin "1") (pinfunction "1_1") (pintype "passive"))
    )
    (net (code "90") (name "Net-(D1-A)") (class "Default")
      (node (ref "D1") (pin "1") (pinfunction "A_1") (pintype "passive"))
      (node (ref "R43") (pin "1") (pinfunction "1_1") (pintype "passive"))
    )
    (net (code "91") (name "Net-(D2-A)") (class "Default")
      (node (ref "D2") (pin "1") (pinfunction "A_1") (pintype "passive"))
      (node (ref "R44") (pin "1") (pinfunction "1_1") (pintype "passive"))
    )
    (net (code "92") (name "Net-(D3-A)") (class "Default")
      (node (ref "D3") (pin "1") (pinfunction "A_1") (pintype "passive"))
      (node (ref "R45") (pin "1") (pinfunction "1_1") (pintype "passive"))
    )
    (net (code "93") (name "Net-(D4-A)") (class "Default")
      (node (ref "D4") (pin "1") (pinfunction "A_1") (pintype "passive"))
      (node (ref "R46") (pin "1") (pinfunction "1_1") (pintype "passive"))
    )
    (net (code "94") (name "Net-(D5-A)") (class "Default")
      (node (ref "D5") (pin "1") (pinfunction "A_1") (pintype "passive"))
      (node (ref "R47") (pin "1") (pinfunction "1_1") (pintype "passive"))
    )
    (net (code "95") (name "VREF") (class "Default")
      (node (ref "R01") (pin "2") (pinfunction "2_2") (pintype "passive"))
    )
    (net (code "96") (name "unconnected-(R31-Pad2)") (class "Default")
      (node (ref "R31") (pin "2") (pinfunction "2_2") (pintype "passive"))
    )
    (net (code "97") (name "unconnected-(R32-Pad2)") (class "Default")
      (node (ref "R32") (pin "2") (pinfunction "2_2") (pintype "passive"))
    )
    (net (code "98") (name "unconnected-(R37-Pad2)") (class "Default")
      (node (ref "R37") (pin "2") (pinfunction "2_2") (pintype "passive"))
    )
    (net (code "99") (name "unconnected-(U1-AD1EVT-Pad86)") (class "Default")
      (node (ref "U1") (pin "86") (pinfunction "AD1EVT_86") (pintype "passive"))
    )
    (net (code "100") (name "unconnected-(U1-AD1IN[0]-Pad60)") (class "Default")
      (node (ref "U1") (pin "60") (pinfunction "AD1IN[0]_60") (pintype "passive"))
    )
    (net (code "101") (name "unconnected-(U1-AD1IN[01]-Pad71)") (class "Default")
      (node (ref "U1") (pin "71") (pinfunction "AD1IN[01]_71") (pintype "passive"))
    )
    (net (code "102") (name "unconnected-(U1-AD1IN[02]-Pad73)") (class "Default")
      (node (ref "U1") (pin "73") (pinfunction "AD1IN[02]_73") (pintype "passive"))
    )
    (net (code "103") (name "unconnected-(U1-AD1IN[03]-Pad74)") (class "Default")
      (node (ref "U1") (pin "74") (pinfunction "AD1IN[03]_74") (pintype "passive"))
    )
    (net (code "104") (name "unconnected-(U1-AD1IN[04]-Pad76)") (class "Default")
      (node (ref "U1") (pin "76") (pinfunction "AD1IN[04]_76") (pintype "passive"))
    )
    (net (code "105") (name "unconnected-(U1-AD1IN[05]-Pad78)") (class "Default")
      (node (ref "U1") (pin "78") (pinfunction "AD1IN[05]_78") (pintype "passive"))
    )
    (net (code "106") (name "unconnected-(U1-AD1IN[06]-Pad80)") (class "Default")
      (node (ref "U1") (pin "80") (pinfunction "AD1IN[06]_80") (pintype "passive"))
    )
    (net (code "107") (name "unconnected-(U1-AD1IN[07]-Pad61)") (class "Default")
      (node (ref "U1") (pin "61") (pinfunction "AD1IN[07]_61") (pintype "passive"))
    )
    (net (code "108") (name "unconnected-(U1-AD1IN[09]_{slash}_AD2IN[09]-Pad70)") (class "Default")
      (node (ref "U1") (pin "70") (pinfunction "AD1IN[09]_/_AD2IN[09]_70") (pintype "passive"))
    )
    (net (code "109") (name "unconnected-(U1-AD1IN[10]_{slash}_AD2IN[10]-Pad72)") (class "Default")
      (node (ref "U1") (pin "72") (pinfunction "AD1IN[10]_/_AD2IN[10]_72") (pintype "passive"))
    )
    (net (code "110") (name "unconnected-(U1-AD1IN[14]_{slash}_AD2IN[14]-Pad82)") (class "Default")
      (node (ref "U1") (pin "82") (pinfunction "AD1IN[14]_/_AD2IN[14]_82") (pintype "passive"))
    )
    (net (code "111") (name "unconnected-(U1-AD1IN[16]_{slash}_AD2IN[0]-Pad58)") (class "Default")
      (node (ref "U1") (pin "58") (pinfunction "AD1IN[16]_/_AD2IN[0]_58") (pintype "passive"))
    )
    (net (code "112") (name "unconnected-(U1-AD1IN[17]_{slash}_AD2IN[01]-Pad59)") (class "Default")
      (node (ref "U1") (pin "59") (pinfunction "AD1IN[17]_/_AD2IN[01]_59") (pintype "passive"))
    )
    (net (code "113") (name "unconnected-(U1-AD1IN[18]_{slash}_AD2IN[02]-Pad62)") (class "Default")
      (node (ref "U1") (pin "62") (pinfunction "AD1IN[18]_/_AD2IN[02]_62") (pintype "passive"))
    )
    (net (code "114") (name "unconnected-(U1-AD1IN[19]_{slash}_AD2IN[03]-Pad63)") (class "Default")
      (node (ref "U1") (pin "63") (pinfunction "AD1IN[19]_/_AD2IN[03]_63") (pintype "passive"))
    )
    (net (code "115") (name "unconnected-(U1-AD1IN[20]_{slash}_AD2IN[04]-Pad64)") (class "Default")
      (node (ref "U1") (pin "64") (pinfunction "AD1IN[20]_/_AD2IN[04]_64") (pintype "passive"))
    )
    (net (code "116") (name "unconnected-(U1-AD1IN[21]_{slash}_AD2IN[05]-Pad65)") (class "Default")
      (node (ref "U1") (pin "65") (pinfunction "AD1IN[21]_/_AD2IN[05]_65") (pintype "passive"))
    )
    (net (code "117") (name "unconnected-(U1-AD1IN[22]_{slash}_AD2IN[06]-Pad81)") (class "Default")
      (node (ref "U1") (pin "81") (pinfunction "AD1IN[22]_/_AD2IN[06]_81") (pintype "passive"))
    )
    (net (code "118") (name "unconnected-(U1-CAN1RX-Pad90)") (class "Default")
      (node (ref "U1") (pin "90") (pinfunction "CAN1RX_90") (pintype "passive"))
    )
    (net (code "119") (name "unconnected-(U1-CAN1TX-Pad89)") (class "Default")
      (node (ref "U1") (pin "89") (pinfunction "CAN1TX_89") (pintype "passive"))
    )
    (net (code "120") (name "unconnected-(U1-CAN2RX-Pad129)") (class "Default")
      (node (ref "U1") (pin "129") (pinfunction "CAN2RX_129") (pintype "passive"))
    )
    (net (code "121") (name "unconnected-(U1-CAN2TX-Pad128)") (class "Default")
      (node (ref "U1") (pin "128") (pinfunction "CAN2TX_128") (pintype "passive"))
    )
    (net (code "122") (name "unconnected-(U1-CAN3RX-Pad12)") (class "Default")
      (node (ref "U1") (pin "12") (pinfunction "CAN3RX_12") (pintype "passive"))
    )
    (net (code "123") (name "unconnected-(U1-CAN3TX-Pad13)") (class "Default")
      (node (ref "U1") (pin "13") (pinfunction "CAN3TX_13") (pintype "passive"))
    )
    (net (code "124") (name "unconnected-(U1-ECLK-Pad119)") (class "Default")
      (node (ref "U1") (pin "119") (pinfunction "ECLK_119") (pintype "passive"))
    )
    (net (code "125") (name "unconnected-(U1-FLTP1-Pad7)") (class "Default")
      (node (ref "U1") (pin "7") (pinfunction "FLTP1_7") (pintype "passive"))
    )
    (net (code "126") (name "unconnected-(U1-FLTP2-Pad8)") (class "Default")
      (node (ref "U1") (pin "8") (pinfunction "FLTP2_8") (pintype "passive"))
    )
    (net (code "127") (name "unconnected-(U1-KELVIN_GND-Pad19)") (class "Default")
      (node (ref "U1") (pin "19") (pinfunction "KELVIN_GND_19") (pintype "passive"))
    )
    (net (code "128") (name "unconnected-(U1-MIBSPI3CLK-Pad53)") (class "Default")
      (node (ref "U1") (pin "53") (pinfunction "MIBSPI3CLK_53") (pintype "passive"))
    )
    (net (code "129") (name "unconnected-(U1-MIBSPI3NCS[1]-Pad37)") (class "Default")
      (node (ref "U1") (pin "37") (pinfunction "MIBSPI3NCS[1]_37") (pintype "passive"))
    )
    (net (code "130") (name "unconnected-(U1-MIBSPI3NENA-Pad54)") (class "Default")
      (node (ref "U1") (pin "54") (pinfunction "MIBSPI3NENA_54") (pintype "passive"))
    )
    (net (code "131") (name "unconnected-(U1-MIBSPI3SIMO-Pad52)") (class "Default")
      (node (ref "U1") (pin "52") (pinfunction "MIBSPI3SIMO_52") (pintype "passive"))
    )
    (net (code "132") (name "unconnected-(U1-MIBSPI3SOMI-Pad51)") (class "Default")
      (node (ref "U1") (pin "51") (pinfunction "MIBSPI3SOMI_51") (pintype "passive"))
    )
    (net (code "133") (name "unconnected-(U1-MIBSPI5CLK-Pad100)") (class "Default")
      (node (ref "U1") (pin "100") (pinfunction "MIBSPI5CLK_100") (pintype "passive"))
    )
    (net (code "134") (name "unconnected-(U1-MIBSPI5NENA-Pad97)") (class "Default")
      (node (ref "U1") (pin "97") (pinfunction "MIBSPI5NENA_97") (pintype "passive"))
    )
    (net (code "135") (name "unconnected-(U1-MIBSPI5SIMO[0]-Pad99)") (class "Default")
      (node (ref "U1") (pin "99") (pinfunction "MIBSPI5SIMO[0]_99") (pintype "passive"))
    )
    (net (code "136") (name "unconnected-(U1-MIBSPI5SOMI[0]-Pad98)") (class "Default")
      (node (ref "U1") (pin "98") (pinfunction "MIBSPI5SOMI[0]_98") (pintype "passive"))
    )
    (net (code "137") (name "unconnected-(U1-N2HET1[01]-Pad23)") (class "Default")
      (node (ref "U1") (pin "23") (pinfunction "N2HET1[01]_23") (pintype "passive"))
    )
    (net (code "138") (name "unconnected-(U1-N2HET1[03]-Pad24)") (class "Default")
      (node (ref "U1") (pin "24") (pinfunction "N2HET1[03]_24") (pintype "passive"))
    )
    (net (code "139") (name "unconnected-(U1-N2HET1[06]-Pad38)") (class "Default")
      (node (ref "U1") (pin "38") (pinfunction "N2HET1[06]_38") (pintype "passive"))
    )
    (net (code "140") (name "unconnected-(U1-N2HET1[07]-Pad33)") (class "Default")
      (node (ref "U1") (pin "33") (pinfunction "N2HET1[07]_33") (pintype "passive"))
    )
    (net (code "141") (name "unconnected-(U1-N2HET1[08]-Pad106)") (class "Default")
      (node (ref "U1") (pin "106") (pinfunction "N2HET1[08]_106") (pintype "passive"))
    )
    (net (code "142") (name "unconnected-(U1-N2HET1[09]-Pad35)") (class "Default")
      (node (ref "U1") (pin "35") (pinfunction "N2HET1[09]_35") (pintype "passive"))
    )
    (net (code "143") (name "unconnected-(U1-N2HET1[10]-Pad118)") (class "Default")
      (node (ref "U1") (pin "118") (pinfunction "N2HET1[10]_118") (pintype "passive"))
    )
    (net (code "144") (name "unconnected-(U1-N2HET1[11]-Pad6)") (class "Default")
      (node (ref "U1") (pin "6") (pinfunction "N2HET1[11]_6") (pintype "passive"))
    )
    (net (code "145") (name "unconnected-(U1-N2HET1[12]-Pad124)") (class "Default")
      (node (ref "U1") (pin "124") (pinfunction "N2HET1[12]_124") (pintype "passive"))
    )
    (net (code "146") (name "unconnected-(U1-N2HET1[13]-Pad39)") (class "Default")
      (node (ref "U1") (pin "39") (pinfunction "N2HET1[13]_39") (pintype "passive"))
    )
    (net (code "147") (name "unconnected-(U1-N2HET1[14]-Pad125)") (class "Default")
      (node (ref "U1") (pin "125") (pinfunction "N2HET1[14]_125") (pintype "passive"))
    )
    (net (code "148") (name "unconnected-(U1-N2HET1[15]-Pad41)") (class "Default")
      (node (ref "U1") (pin "41") (pinfunction "N2HET1[15]_41") (pintype "passive"))
    )
    (net (code "149") (name "unconnected-(U1-N2HET1[16]-Pad139)") (class "Default")
      (node (ref "U1") (pin "139") (pinfunction "N2HET1[16]_139") (pintype "passive"))
    )
    (net (code "150") (name "unconnected-(U1-N2HET1[18]-Pad140)") (class "Default")
      (node (ref "U1") (pin "140") (pinfunction "N2HET1[18]_140") (pintype "passive"))
    )
    (net (code "151") (name "unconnected-(U1-N2HET1[20]-Pad141)") (class "Default")
      (node (ref "U1") (pin "141") (pinfunction "N2HET1[20]_141") (pintype "passive"))
    )
    (net (code "152") (name "unconnected-(U1-N2HET1[22]-Pad15)") (class "Default")
      (node (ref "U1") (pin "15") (pinfunction "N2HET1[22]_15") (pintype "passive"))
    )
    (net (code "153") (name "unconnected-(U1-N2HET1[24]-Pad91)") (class "Default")
      (node (ref "U1") (pin "91") (pinfunction "N2HET1[24]_91") (pintype "passive"))
    )
    (net (code "154") (name "unconnected-(U1-N2HET1[26]-Pad92)") (class "Default")
      (node (ref "U1") (pin "92") (pinfunction "N2HET1[26]_92") (pintype "passive"))
    )
    (net (code "155") (name "unconnected-(U1-N2HET1[28]-Pad107)") (class "Default")
      (node (ref "U1") (pin "107") (pinfunction "N2HET1[28]_107") (pintype "passive"))
    )
    (net (code "156") (name "unconnected-(U1-N2HET1[30]-Pad127)") (class "Default")
      (node (ref "U1") (pin "127") (pinfunction "N2HET1[30]_127") (pintype "passive"))
    )
    (net (code "157") (name "unconnected-(U1-OSCOUT-Pad20)") (class "Default")
      (node (ref "U1") (pin "20") (pinfunction "OSCOUT_20") (pintype "passive"))
    )
    (net (code "158") (name "unconnected-(U6-EOH-Pad1)") (class "Default")
      (node (ref "U6") (pin "1") (pinfunction "EOH_1") (pintype "passive"))
    )
    (net (code "159") (name "unconnected-(U7-CT-Pad5)") (class "Default")
      (node (ref "U7") (pin "5") (pinfunction "CT_5") (pintype "passive"))
    )
  )
)
